# apic_shield_motor.net
KiCad netlist of a schematic drawn in EAGLE
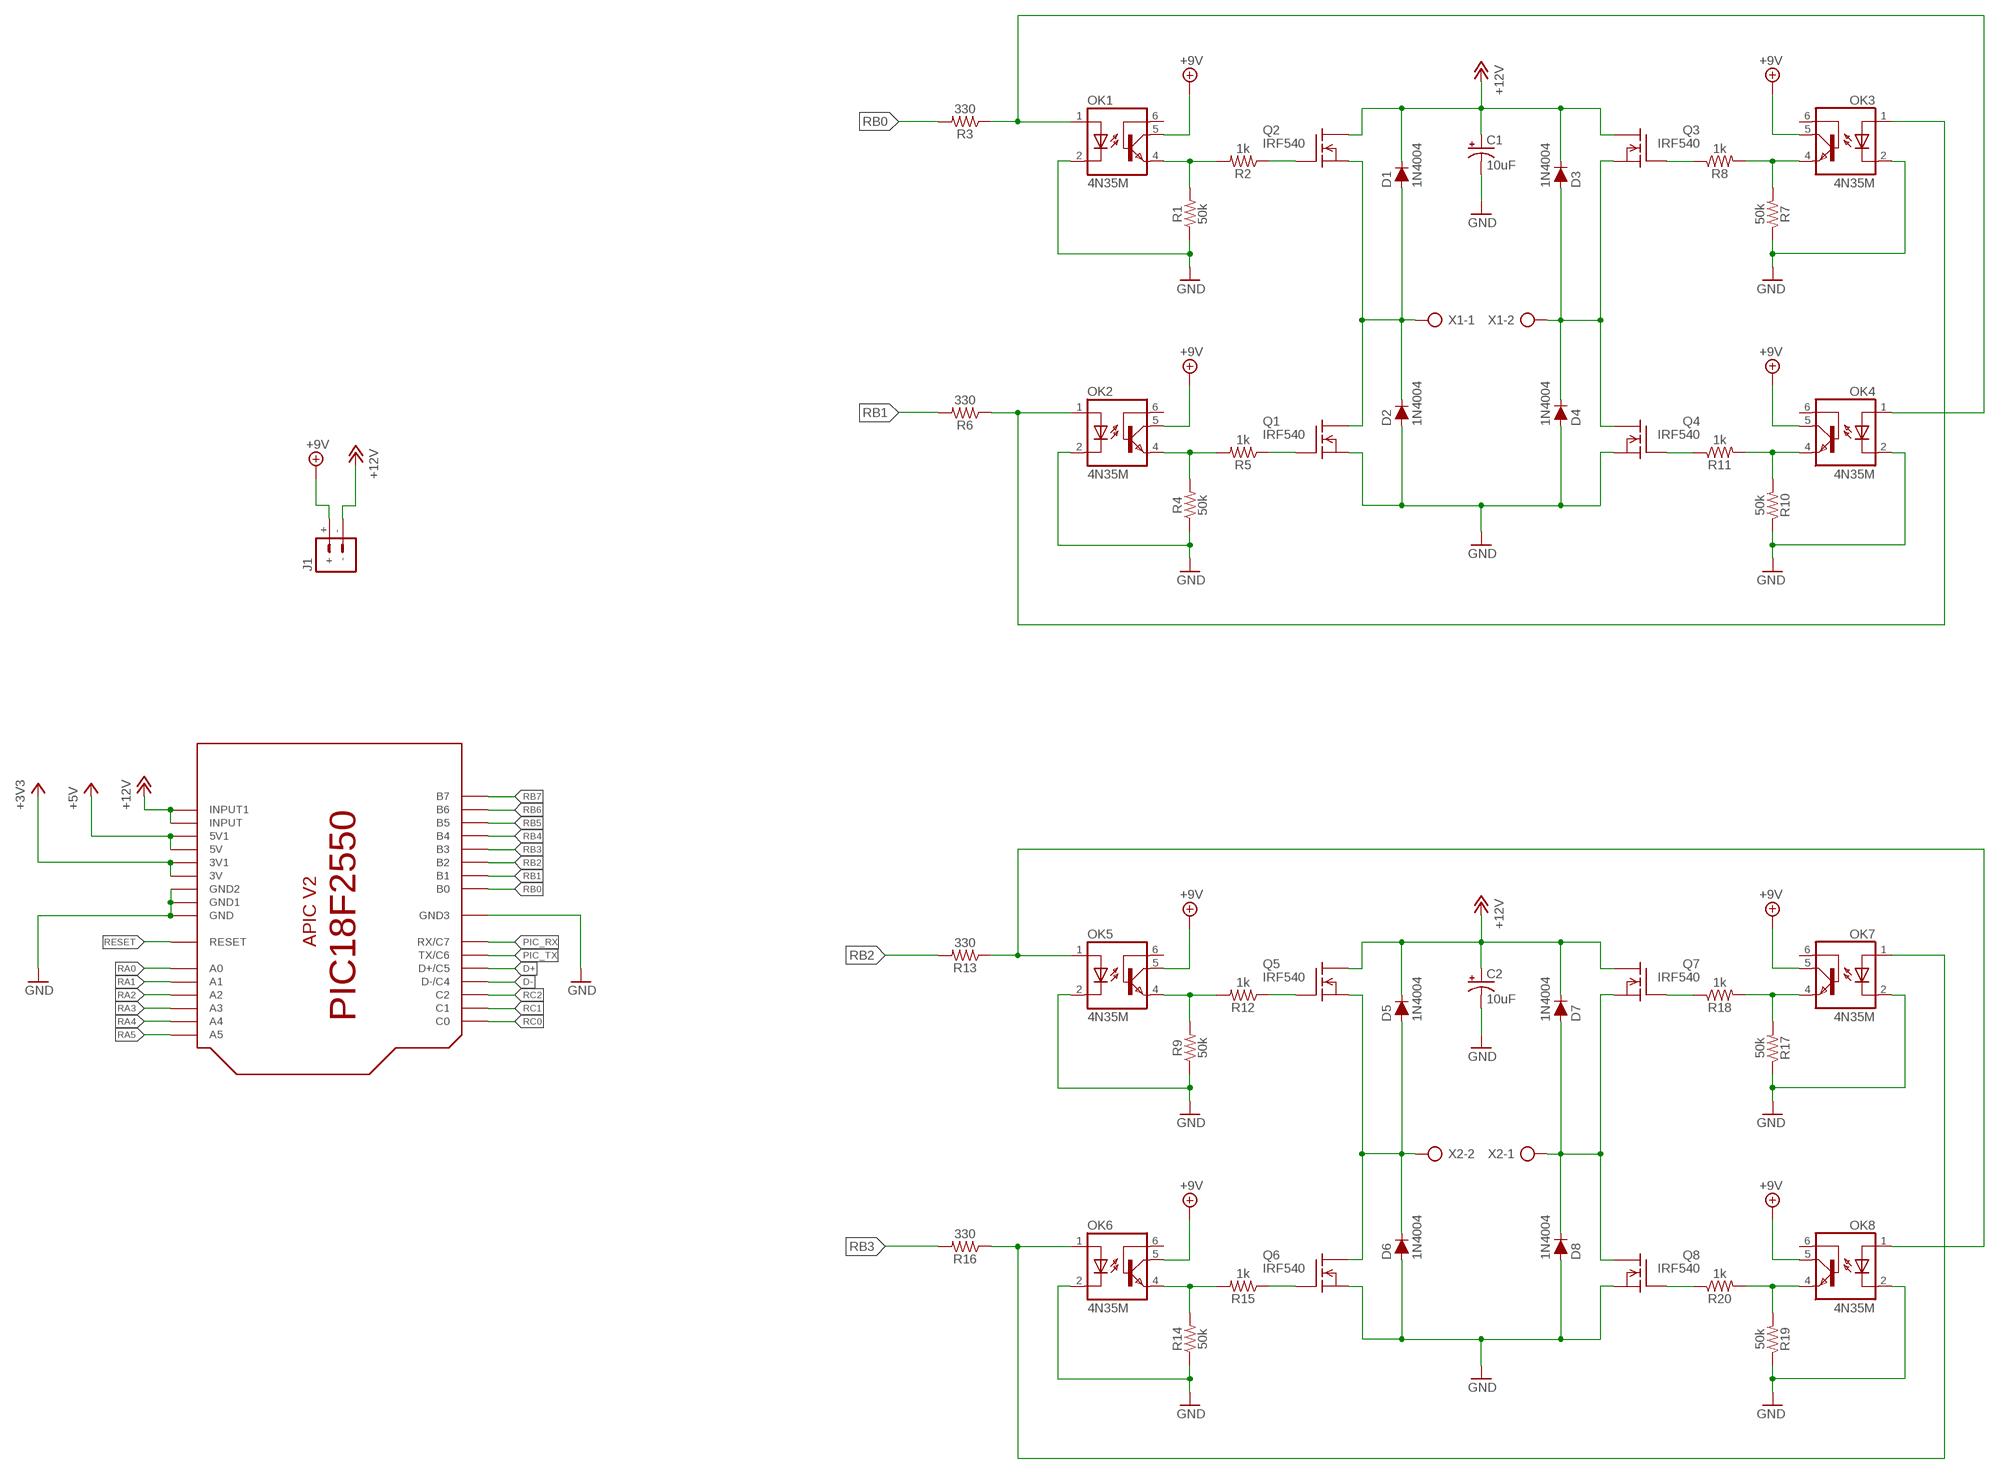
[diagram p0: schematic, sheet 1]

(export (version "E")
  (design (tool "Eeschema 10.0.6"))
  (components
    (comp (ref "C1")
      (value "10uF")
      (footprint "eagle-import:CPOL-RADIAL-2.5MM-5MM")
      (libsource (lib "eagle-import") (part "10UF-POLAR-RADIAL-2.5MM-25V-20%"))
    )
    (comp (ref "C2")
      (value "10uF")
      (footprint "eagle-import:CPOL-RADIAL-2.5MM-5MM")
      (libsource (lib "eagle-import") (part "10UF-POLAR-RADIAL-2.5MM-25V-20%"))
    )
    (comp (ref "D1")
      (value "1N4004")
      (footprint "eagle-import:DIODE-1N4001")
      (libsource (lib "eagle-import") (part "DIODE-PTH"))
    )
    (comp (ref "D2")
      (value "1N4004")
      (footprint "eagle-import:DIODE-1N4001")
      (libsource (lib "eagle-import") (part "DIODE-PTH"))
    )
    (comp (ref "D3")
      (value "1N4004")
      (footprint "eagle-import:DIODE-1N4001")
      (libsource (lib "eagle-import") (part "DIODE-PTH"))
    )
    (comp (ref "D4")
      (value "1N4004")
      (footprint "eagle-import:DIODE-1N4001")
      (libsource (lib "eagle-import") (part "DIODE-PTH"))
    )
    (comp (ref "D5")
      (value "1N4004")
      (footprint "eagle-import:DIODE-1N4001")
      (libsource (lib "eagle-import") (part "DIODE-PTH"))
    )
    (comp (ref "D6")
      (value "1N4004")
      (footprint "eagle-import:DIODE-1N4001")
      (libsource (lib "eagle-import") (part "DIODE-PTH"))
    )
    (comp (ref "D7")
      (value "1N4004")
      (footprint "eagle-import:DIODE-1N4001")
      (libsource (lib "eagle-import") (part "DIODE-PTH"))
    )
    (comp (ref "D8")
      (value "1N4004")
      (footprint "eagle-import:DIODE-1N4001")
      (libsource (lib "eagle-import") (part "DIODE-PTH"))
    )
    (comp (ref "J1")
      (value "BATTERY_CONN_DEANS")
      (footprint "eagle-import:DEANS")
      (libsource (lib "eagle-import") (part "BATTERY_CONN_DEANS"))
    )
    (comp (ref "OK1")
      (value "4N35M")
      (footprint "eagle-import:DIL06")
      (fields (field (name "MPN") "4N35-M"))
      (libsource (lib "eagle-import") (part "4N?M35"))
    )
    (comp (ref "OK2")
      (value "4N35M")
      (footprint "eagle-import:DIL06")
      (fields (field (name "MPN") "4N35-M"))
      (libsource (lib "eagle-import") (part "4N?M35"))
    )
    (comp (ref "OK3")
      (value "4N35M")
      (footprint "eagle-import:DIL06")
      (fields (field (name "MPN") "4N35-M"))
      (libsource (lib "eagle-import") (part "4N?M35"))
    )
    (comp (ref "OK4")
      (value "4N35M")
      (footprint "eagle-import:DIL06")
      (fields (field (name "MPN") "4N35-M"))
      (libsource (lib "eagle-import") (part "4N?M35"))
    )
    (comp (ref "OK5")
      (value "4N35M")
      (footprint "eagle-import:DIL06")
      (fields (field (name "MPN") "4N35-M"))
      (libsource (lib "eagle-import") (part "4N?M35"))
    )
    (comp (ref "OK6")
      (value "4N35M")
      (footprint "eagle-import:DIL06")
      (fields (field (name "MPN") "4N35-M"))
      (libsource (lib "eagle-import") (part "4N?M35"))
    )
    (comp (ref "OK7")
      (value "4N35M")
      (footprint "eagle-import:DIL06")
      (fields (field (name "MPN") "4N35-M"))
      (libsource (lib "eagle-import") (part "4N?M35"))
    )
    (comp (ref "OK8")
      (value "4N35M")
      (footprint "eagle-import:DIL06")
      (fields (field (name "MPN") "4N35-M"))
      (libsource (lib "eagle-import") (part "4N?M35"))
    )
    (comp (ref "Q1")
      (value "IRF540")
      (footprint "eagle-import:TO220V")
      (libsource (lib "eagle-import") (part "IRF540"))
    )
    (comp (ref "Q2")
      (value "IRF540")
      (footprint "eagle-import:TO220V")
      (libsource (lib "eagle-import") (part "IRF540"))
    )
    (comp (ref "Q3")
      (value "IRF540")
      (footprint "eagle-import:TO220V")
      (libsource (lib "eagle-import") (part "IRF540"))
    )
    (comp (ref "Q4")
      (value "IRF540")
      (footprint "eagle-import:TO220V")
      (libsource (lib "eagle-import") (part "IRF540"))
    )
    (comp (ref "Q5")
      (value "IRF540")
      (footprint "eagle-import:TO220V")
      (libsource (lib "eagle-import") (part "IRF540"))
    )
    (comp (ref "Q6")
      (value "IRF540")
      (footprint "eagle-import:TO220V")
      (libsource (lib "eagle-import") (part "IRF540"))
    )
    (comp (ref "Q7")
      (value "IRF540")
      (footprint "eagle-import:TO220V")
      (libsource (lib "eagle-import") (part "IRF540"))
    )
    (comp (ref "Q8")
      (value "IRF540")
      (footprint "eagle-import:TO220V")
      (libsource (lib "eagle-import") (part "IRF540"))
    )
    (comp (ref "R1")
      (value "50k")
      (footprint "eagle-import:AXIAL-0.3")
      (libsource (lib "eagle-import") (part "1KOHM-HORIZ-1/4W-1%"))
    )
    (comp (ref "R2")
      (value "1k")
      (footprint "eagle-import:AXIAL-0.3")
      (libsource (lib "eagle-import") (part "1KOHM-HORIZ-1/4W-1%"))
    )
    (comp (ref "R3")
      (value "330")
      (footprint "eagle-import:AXIAL-0.3")
      (libsource (lib "eagle-import") (part "1KOHM-HORIZ-1/4W-1%"))
    )
    (comp (ref "R4")
      (value "50k")
      (footprint "eagle-import:AXIAL-0.3")
      (libsource (lib "eagle-import") (part "1KOHM-HORIZ-1/4W-1%"))
    )
    (comp (ref "R5")
      (value "1k")
      (footprint "eagle-import:AXIAL-0.3")
      (libsource (lib "eagle-import") (part "1KOHM-HORIZ-1/4W-1%"))
    )
    (comp (ref "R6")
      (value "330")
      (footprint "eagle-import:AXIAL-0.3")
      (libsource (lib "eagle-import") (part "1KOHM-HORIZ-1/4W-1%"))
    )
    (comp (ref "R7")
      (value "50k")
      (footprint "eagle-import:AXIAL-0.3")
      (libsource (lib "eagle-import") (part "1KOHM-HORIZ-1/4W-1%"))
    )
    (comp (ref "R8")
      (value "1k")
      (footprint "eagle-import:AXIAL-0.3")
      (libsource (lib "eagle-import") (part "1KOHM-HORIZ-1/4W-1%"))
    )
    (comp (ref "R9")
      (value "50k")
      (footprint "eagle-import:AXIAL-0.3")
      (libsource (lib "eagle-import") (part "1KOHM-HORIZ-1/4W-1%"))
    )
    (comp (ref "R10")
      (value "50k")
      (footprint "eagle-import:AXIAL-0.3")
      (libsource (lib "eagle-import") (part "1KOHM-HORIZ-1/4W-1%"))
    )
    (comp (ref "R11")
      (value "1k")
      (footprint "eagle-import:AXIAL-0.3")
      (libsource (lib "eagle-import") (part "1KOHM-HORIZ-1/4W-1%"))
    )
    (comp (ref "R12")
      (value "1k")
      (footprint "eagle-import:AXIAL-0.3")
      (libsource (lib "eagle-import") (part "1KOHM-HORIZ-1/4W-1%"))
    )
    (comp (ref "R13")
      (value "330")
      (footprint "eagle-import:AXIAL-0.3")
      (libsource (lib "eagle-import") (part "1KOHM-HORIZ-1/4W-1%"))
    )
    (comp (ref "R14")
      (value "50k")
      (footprint "eagle-import:AXIAL-0.3")
      (libsource (lib "eagle-import") (part "1KOHM-HORIZ-1/4W-1%"))
    )
    (comp (ref "R15")
      (value "1k")
      (footprint "eagle-import:AXIAL-0.3")
      (libsource (lib "eagle-import") (part "1KOHM-HORIZ-1/4W-1%"))
    )
    (comp (ref "R16")
      (value "330")
      (footprint "eagle-import:AXIAL-0.3")
      (libsource (lib "eagle-import") (part "1KOHM-HORIZ-1/4W-1%"))
    )
    (comp (ref "R17")
      (value "50k")
      (footprint "eagle-import:AXIAL-0.3")
      (libsource (lib "eagle-import") (part "1KOHM-HORIZ-1/4W-1%"))
    )
    (comp (ref "R18")
      (value "1k")
      (footprint "eagle-import:AXIAL-0.3")
      (libsource (lib "eagle-import") (part "1KOHM-HORIZ-1/4W-1%"))
    )
    (comp (ref "R19")
      (value "50k")
      (footprint "eagle-import:AXIAL-0.3")
      (libsource (lib "eagle-import") (part "1KOHM-HORIZ-1/4W-1%"))
    )
    (comp (ref "R20")
      (value "1k")
      (footprint "eagle-import:AXIAL-0.3")
      (libsource (lib "eagle-import") (part "1KOHM-HORIZ-1/4W-1%"))
    )
    (comp (ref "U$1")
      (value "APIC-18F2550")
      (footprint "eagle-import:APIC-18F2550")
      (libsource (lib "eagle-import") (part "APIC-18F2550"))
    )
    (comp (ref "X1")
      (value "AK500/2-H")
      (footprint "eagle-import:AK500_2-H")
      (libsource (lib "eagle-import") (part "AK500/2-H"))
    )
    (comp (ref "X2")
      (value "AK500/2-H")
      (footprint "eagle-import:AK500_2-H")
      (libsource (lib "eagle-import") (part "AK500/2-H"))
    )
  )
  (nets
    (net (code "1") (name "+3V3") (class "Default")
      (node (ref "U$1") (pin "3V") (pinfunction "3V_3V") (pintype "power_in"))
      (node (ref "U$1") (pin "3V1") (pinfunction "3V1_3V1") (pintype "power_in"))
    )
    (net (code "2") (name "+5V") (class "Default")
      (node (ref "U$1") (pin "5V") (pinfunction "5V_5V") (pintype "power_in"))
      (node (ref "U$1") (pin "5V1") (pinfunction "5V1_5V1") (pintype "power_in"))
    )
    (net (code "3") (name "+9V") (class "Default")
      (node (ref "J1") (pin "+") (pinfunction "+_+") (pintype "passive"))
      (node (ref "OK1") (pin "5") (pinfunction "COL_5") (pintype "passive"))
      (node (ref "OK2") (pin "5") (pinfunction "COL_5") (pintype "passive"))
      (node (ref "OK3") (pin "5") (pinfunction "COL_5") (pintype "passive"))
      (node (ref "OK4") (pin "5") (pinfunction "COL_5") (pintype "passive"))
      (node (ref "OK5") (pin "5") (pinfunction "COL_5") (pintype "passive"))
      (node (ref "OK6") (pin "5") (pinfunction "COL_5") (pintype "passive"))
      (node (ref "OK7") (pin "5") (pinfunction "COL_5") (pintype "passive"))
      (node (ref "OK8") (pin "5") (pinfunction "COL_5") (pintype "passive"))
    )
    (net (code "4") (name "+12V") (class "Default")
      (node (ref "C1") (pin "1") (pinfunction "+_1") (pintype "passive"))
      (node (ref "C2") (pin "1") (pinfunction "+_1") (pintype "passive"))
      (node (ref "D1") (pin "C") (pinfunction "C_C") (pintype "passive"))
      (node (ref "D3") (pin "C") (pinfunction "C_C") (pintype "passive"))
      (node (ref "D5") (pin "C") (pinfunction "C_C") (pintype "passive"))
      (node (ref "D7") (pin "C") (pinfunction "C_C") (pintype "passive"))
      (node (ref "J1") (pin "-") (pinfunction "-_-") (pintype "passive"))
      (node (ref "Q2") (pin "2") (pinfunction "D_2") (pintype "passive"))
      (node (ref "Q3") (pin "2") (pinfunction "D_2") (pintype "passive"))
      (node (ref "Q5") (pin "2") (pinfunction "D_2") (pintype "passive"))
      (node (ref "Q7") (pin "2") (pinfunction "D_2") (pintype "passive"))
      (node (ref "U$1") (pin "INPUT") (pinfunction "INPUT_INPUT") (pintype "power_in"))
      (node (ref "U$1") (pin "INPUT1") (pinfunction "INPUT1_INPUT1") (pintype "power_in"))
    )
    (net (code "5") (name "D+") (class "Default")
      (node (ref "U$1") (pin "C5") (pinfunction "D+/C5_C5") (pintype "bidirectional"))
    )
    (net (code "6") (name "D-") (class "Default")
      (node (ref "U$1") (pin "C4") (pinfunction "D-/C4_C4") (pintype "bidirectional"))
    )
    (net (code "7") (name "GND") (class "Default")
      (node (ref "C1") (pin "2") (pinfunction "-_2") (pintype "passive"))
      (node (ref "C2") (pin "2") (pinfunction "-_2") (pintype "passive"))
      (node (ref "D2") (pin "A") (pinfunction "A_A") (pintype "passive"))
      (node (ref "D4") (pin "A") (pinfunction "A_A") (pintype "passive"))
      (node (ref "D6") (pin "A") (pinfunction "A_A") (pintype "passive"))
      (node (ref "D8") (pin "A") (pinfunction "A_A") (pintype "passive"))
      (node (ref "OK1") (pin "2") (pinfunction "C_2") (pintype "passive"))
      (node (ref "OK2") (pin "2") (pinfunction "C_2") (pintype "passive"))
      (node (ref "OK3") (pin "2") (pinfunction "C_2") (pintype "passive"))
      (node (ref "OK4") (pin "2") (pinfunction "C_2") (pintype "passive"))
      (node (ref "OK5") (pin "2") (pinfunction "C_2") (pintype "passive"))
      (node (ref "OK6") (pin "2") (pinfunction "C_2") (pintype "passive"))
      (node (ref "OK7") (pin "2") (pinfunction "C_2") (pintype "passive"))
      (node (ref "OK8") (pin "2") (pinfunction "C_2") (pintype "passive"))
      (node (ref "Q1") (pin "3") (pinfunction "S_3") (pintype "passive"))
      (node (ref "Q4") (pin "3") (pinfunction "S_3") (pintype "passive"))
      (node (ref "Q6") (pin "3") (pinfunction "S_3") (pintype "passive"))
      (node (ref "Q8") (pin "3") (pinfunction "S_3") (pintype "passive"))
      (node (ref "R1") (pin "P$1") (pinfunction "1_P$1") (pintype "passive"))
      (node (ref "R10") (pin "P$1") (pinfunction "1_P$1") (pintype "passive"))
      (node (ref "R14") (pin "P$1") (pinfunction "1_P$1") (pintype "passive"))
      (node (ref "R17") (pin "P$1") (pinfunction "1_P$1") (pintype "passive"))
      (node (ref "R19") (pin "P$1") (pinfunction "1_P$1") (pintype "passive"))
      (node (ref "R4") (pin "P$1") (pinfunction "1_P$1") (pintype "passive"))
      (node (ref "R7") (pin "P$1") (pinfunction "1_P$1") (pintype "passive"))
      (node (ref "R9") (pin "P$1") (pinfunction "1_P$1") (pintype "passive"))
      (node (ref "U$1") (pin "GND") (pinfunction "GND_GND") (pintype "power_in"))
      (node (ref "U$1") (pin "GND1") (pinfunction "GND1_GND1") (pintype "power_in"))
      (node (ref "U$1") (pin "GND2") (pinfunction "GND2_GND2") (pintype "power_in"))
      (node (ref "U$1") (pin "GND3") (pinfunction "GND3_GND3") (pintype "power_in"))
    )
    (net (code "8") (name "Net-(OK1-A)") (class "Default")
      (node (ref "OK1") (pin "1") (pinfunction "A_1") (pintype "passive"))
      (node (ref "OK4") (pin "1") (pinfunction "A_1") (pintype "passive"))
      (node (ref "R3") (pin "P$1") (pinfunction "1_P$1") (pintype "passive"))
    )
    (net (code "9") (name "Net-(OK1-EMI)") (class "Default")
      (node (ref "OK1") (pin "4") (pinfunction "EMI_4") (pintype "passive"))
      (node (ref "R1") (pin "P$2") (pinfunction "2_P$2") (pintype "passive"))
      (node (ref "R2") (pin "P$2") (pinfunction "2_P$2") (pintype "passive"))
    )
    (net (code "10") (name "Net-(OK2-A)") (class "Default")
      (node (ref "OK2") (pin "1") (pinfunction "A_1") (pintype "passive"))
      (node (ref "OK3") (pin "1") (pinfunction "A_1") (pintype "passive"))
      (node (ref "R6") (pin "P$1") (pinfunction "1_P$1") (pintype "passive"))
    )
    (net (code "11") (name "Net-(OK2-EMI)") (class "Default")
      (node (ref "OK2") (pin "4") (pinfunction "EMI_4") (pintype "passive"))
      (node (ref "R4") (pin "P$2") (pinfunction "2_P$2") (pintype "passive"))
      (node (ref "R5") (pin "P$2") (pinfunction "2_P$2") (pintype "passive"))
    )
    (net (code "12") (name "Net-(OK3-EMI)") (class "Default")
      (node (ref "OK3") (pin "4") (pinfunction "EMI_4") (pintype "passive"))
      (node (ref "R7") (pin "P$2") (pinfunction "2_P$2") (pintype "passive"))
      (node (ref "R8") (pin "P$2") (pinfunction "2_P$2") (pintype "passive"))
    )
    (net (code "13") (name "Net-(OK4-EMI)") (class "Default")
      (node (ref "OK4") (pin "4") (pinfunction "EMI_4") (pintype "passive"))
      (node (ref "R10") (pin "P$2") (pinfunction "2_P$2") (pintype "passive"))
      (node (ref "R11") (pin "P$2") (pinfunction "2_P$2") (pintype "passive"))
    )
    (net (code "14") (name "Net-(OK5-A)") (class "Default")
      (node (ref "OK5") (pin "1") (pinfunction "A_1") (pintype "passive"))
      (node (ref "OK8") (pin "1") (pinfunction "A_1") (pintype "passive"))
      (node (ref "R13") (pin "P$1") (pinfunction "1_P$1") (pintype "passive"))
    )
    (net (code "15") (name "Net-(OK5-EMI)") (class "Default")
      (node (ref "OK5") (pin "4") (pinfunction "EMI_4") (pintype "passive"))
      (node (ref "R12") (pin "P$2") (pinfunction "2_P$2") (pintype "passive"))
      (node (ref "R9") (pin "P$2") (pinfunction "2_P$2") (pintype "passive"))
    )
    (net (code "16") (name "Net-(OK6-A)") (class "Default")
      (node (ref "OK6") (pin "1") (pinfunction "A_1") (pintype "passive"))
      (node (ref "OK7") (pin "1") (pinfunction "A_1") (pintype "passive"))
      (node (ref "R16") (pin "P$1") (pinfunction "1_P$1") (pintype "passive"))
    )
    (net (code "17") (name "Net-(OK6-EMI)") (class "Default")
      (node (ref "OK6") (pin "4") (pinfunction "EMI_4") (pintype "passive"))
      (node (ref "R14") (pin "P$2") (pinfunction "2_P$2") (pintype "passive"))
      (node (ref "R15") (pin "P$2") (pinfunction "2_P$2") (pintype "passive"))
    )
    (net (code "18") (name "Net-(OK7-EMI)") (class "Default")
      (node (ref "OK7") (pin "4") (pinfunction "EMI_4") (pintype "passive"))
      (node (ref "R17") (pin "P$2") (pinfunction "2_P$2") (pintype "passive"))
      (node (ref "R18") (pin "P$2") (pinfunction "2_P$2") (pintype "passive"))
    )
    (net (code "19") (name "Net-(OK8-EMI)") (class "Default")
      (node (ref "OK8") (pin "4") (pinfunction "EMI_4") (pintype "passive"))
      (node (ref "R19") (pin "P$2") (pinfunction "2_P$2") (pintype "passive"))
      (node (ref "R20") (pin "P$2") (pinfunction "2_P$2") (pintype "passive"))
    )
    (net (code "20") (name "Net-(Q1-D)") (class "Default")
      (node (ref "D1") (pin "A") (pinfunction "A_A") (pintype "passive"))
      (node (ref "D2") (pin "C") (pinfunction "C_C") (pintype "passive"))
      (node (ref "Q1") (pin "2") (pinfunction "D_2") (pintype "passive"))
      (node (ref "Q2") (pin "3") (pinfunction "S_3") (pintype "passive"))
      (node (ref "X1") (pin "1") (pinfunction "KL_1") (pintype "passive"))
    )
    (net (code "21") (name "Net-(Q1-G)") (class "Default")
      (node (ref "Q1") (pin "1") (pinfunction "G_1") (pintype "passive"))
      (node (ref "R5") (pin "P$1") (pinfunction "1_P$1") (pintype "passive"))
    )
    (net (code "22") (name "Net-(Q2-G)") (class "Default")
      (node (ref "Q2") (pin "1") (pinfunction "G_1") (pintype "passive"))
      (node (ref "R2") (pin "P$1") (pinfunction "1_P$1") (pintype "passive"))
    )
    (net (code "23") (name "Net-(Q3-G)") (class "Default")
      (node (ref "Q3") (pin "1") (pinfunction "G_1") (pintype "passive"))
      (node (ref "R8") (pin "P$1") (pinfunction "1_P$1") (pintype "passive"))
    )
    (net (code "24") (name "Net-(Q3-S)") (class "Default")
      (node (ref "D3") (pin "A") (pinfunction "A_A") (pintype "passive"))
      (node (ref "D4") (pin "C") (pinfunction "C_C") (pintype "passive"))
      (node (ref "Q3") (pin "3") (pinfunction "S_3") (pintype "passive"))
      (node (ref "Q4") (pin "2") (pinfunction "D_2") (pintype "passive"))
      (node (ref "X1") (pin "2") (pinfunction "KL_2") (pintype "passive"))
    )
    (net (code "25") (name "Net-(Q4-G)") (class "Default")
      (node (ref "Q4") (pin "1") (pinfunction "G_1") (pintype "passive"))
      (node (ref "R11") (pin "P$1") (pinfunction "1_P$1") (pintype "passive"))
    )
    (net (code "26") (name "Net-(Q5-G)") (class "Default")
      (node (ref "Q5") (pin "1") (pinfunction "G_1") (pintype "passive"))
      (node (ref "R12") (pin "P$1") (pinfunction "1_P$1") (pintype "passive"))
    )
    (net (code "27") (name "Net-(Q5-S)") (class "Default")
      (node (ref "D5") (pin "A") (pinfunction "A_A") (pintype "passive"))
      (node (ref "D6") (pin "C") (pinfunction "C_C") (pintype "passive"))
      (node (ref "Q5") (pin "3") (pinfunction "S_3") (pintype "passive"))
      (node (ref "Q6") (pin "2") (pinfunction "D_2") (pintype "passive"))
      (node (ref "X2") (pin "2") (pinfunction "KL_2") (pintype "passive"))
    )
    (net (code "28") (name "Net-(Q6-G)") (class "Default")
      (node (ref "Q6") (pin "1") (pinfunction "G_1") (pintype "passive"))
      (node (ref "R15") (pin "P$1") (pinfunction "1_P$1") (pintype "passive"))
    )
    (net (code "29") (name "Net-(Q7-G)") (class "Default")
      (node (ref "Q7") (pin "1") (pinfunction "G_1") (pintype "passive"))
      (node (ref "R18") (pin "P$1") (pinfunction "1_P$1") (pintype "passive"))
    )
    (net (code "30") (name "Net-(Q7-S)") (class "Default")
      (node (ref "D7") (pin "A") (pinfunction "A_A") (pintype "passive"))
      (node (ref "D8") (pin "C") (pinfunction "C_C") (pintype "passive"))
      (node (ref "Q7") (pin "3") (pinfunction "S_3") (pintype "passive"))
      (node (ref "Q8") (pin "2") (pinfunction "D_2") (pintype "passive"))
      (node (ref "X2") (pin "1") (pinfunction "KL_1") (pintype "passive"))
    )
    (net (code "31") (name "Net-(Q8-G)") (class "Default")
      (node (ref "Q8") (pin "1") (pinfunction "G_1") (pintype "passive"))
      (node (ref "R20") (pin "P$1") (pinfunction "1_P$1") (pintype "passive"))
    )
    (net (code "32") (name "PIC_RX") (class "Default")
      (node (ref "U$1") (pin "C7") (pinfunction "RX/C7_C7") (pintype "bidirectional"))
    )
    (net (code "33") (name "PIC_TX") (class "Default")
      (node (ref "U$1") (pin "C6") (pinfunction "TX/C6_C6") (pintype "bidirectional"))
    )
    (net (code "34") (name "RA0") (class "Default")
      (node (ref "U$1") (pin "A0") (pinfunction "A0_A0") (pintype "bidirectional"))
    )
    (net (code "35") (name "RA1") (class "Default")
      (node (ref "U$1") (pin "A1") (pinfunction "A1_A1") (pintype "bidirectional"))
    )
    (net (code "36") (name "RA2") (class "Default")
      (node (ref "U$1") (pin "A2") (pinfunction "A2_A2") (pintype "bidirectional"))
    )
    (net (code "37") (name "RA3") (class "Default")
      (node (ref "U$1") (pin "A3") (pinfunction "A3_A3") (pintype "bidirectional"))
    )
    (net (code "38") (name "RA4") (class "Default")
      (node (ref "U$1") (pin "A4") (pinfunction "A4_A4") (pintype "bidirectional"))
    )
    (net (code "39") (name "RA5") (class "Default")
      (node (ref "U$1") (pin "A5") (pinfunction "A5_A5") (pintype "bidirectional"))
    )
    (net (code "40") (name "RB0") (class "Default")
      (node (ref "R3") (pin "P$2") (pinfunction "2_P$2") (pintype "passive"))
      (node (ref "U$1") (pin "B0") (pinfunction "B0_B0") (pintype "bidirectional"))
    )
    (net (code "41") (name "RB1") (class "Default")
      (node (ref "R6") (pin "P$2") (pinfunction "2_P$2") (pintype "passive"))
      (node (ref "U$1") (pin "B1") (pinfunction "B1_B1") (pintype "bidirectional"))
    )
    (net (code "42") (name "RB2") (class "Default")
      (node (ref "R13") (pin "P$2") (pinfunction "2_P$2") (pintype "passive"))
      (node (ref "U$1") (pin "B2") (pinfunction "B2_B2") (pintype "bidirectional"))
    )
    (net (code "43") (name "RB3") (class "Default")
      (node (ref "R16") (pin "P$2") (pinfunction "2_P$2") (pintype "passive"))
      (node (ref "U$1") (pin "B3") (pinfunction "B3_B3") (pintype "bidirectional"))
    )
    (net (code "44") (name "RB4") (class "Default")
      (node (ref "U$1") (pin "B4") (pinfunction "B4_B4") (pintype "bidirectional"))
    )
    (net (code "45") (name "RB5") (class "Default")
      (node (ref "U$1") (pin "B5") (pinfunction "B5_B5") (pintype "bidirectional"))
    )
    (net (code "46") (name "RB6") (class "Default")
      (node (ref "U$1") (pin "B6") (pinfunction "B6_B6") (pintype "bidirectional"))
    )
    (net (code "47") (name "RB7") (class "Default")
      (node (ref "U$1") (pin "B7") (pinfunction "B7_B7") (pintype "bidirectional"))
    )
    (net (code "48") (name "RC0") (class "Default")
      (node (ref "U$1") (pin "C0") (pinfunction "C0_C0") (pintype "bidirectional"))
    )
    (net (code "49") (name "RC1") (class "Default")
      (node (ref "U$1") (pin "C1") (pinfunction "C1_C1") (pintype "bidirectional"))
    )
    (net (code "50") (name "RC2") (class "Default")
      (node (ref "U$1") (pin "C2") (pinfunction "C2_C2") (pintype "bidirectional"))
    )
    (net (code "51") (name "RESET") (class "Default")
      (node (ref "U$1") (pin "RESET") (pinfunction "RESET_RESET") (pintype "bidirectional"))
    )
    (net (code "52") (name "unconnected-(OK1-BAS-Pad6)") (class "Default")
      (node (ref "OK1") (pin "6") (pinfunction "BAS_6") (pintype "passive"))
    )
    (net (code "53") (name "unconnected-(OK2-BAS-Pad6)") (class "Default")
      (node (ref "OK2") (pin "6") (pinfunction "BAS_6") (pintype "passive"))
    )
    (net (code "54") (name "unconnected-(OK3-BAS-Pad6)") (class "Default")
      (node (ref "OK3") (pin "6") (pinfunction "BAS_6") (pintype "passive"))
    )
    (net (code "55") (name "unconnected-(OK4-BAS-Pad6)") (class "Default")
      (node (ref "OK4") (pin "6") (pinfunction "BAS_6") (pintype "passive"))
    )
    (net (code "56") (name "unconnected-(OK5-BAS-Pad6)") (class "Default")
      (node (ref "OK5") (pin "6") (pinfunction "BAS_6") (pintype "passive"))
    )
    (net (code "57") (name "unconnected-(OK6-BAS-Pad6)") (class "Default")
      (node (ref "OK6") (pin "6") (pinfunction "BAS_6") (pintype "passive"))
    )
    (net (code "58") (name "unconnected-(OK7-BAS-Pad6)") (class "Default")
      (node (ref "OK7") (pin "6") (pinfunction "BAS_6") (pintype "passive"))
    )
    (net (code "59") (name "unconnected-(OK8-BAS-Pad6)") (class "Default")
      (node (ref "OK8") (pin "6") (pinfunction "BAS_6") (pintype "passive"))
    )
  )
)
